# gatedriver_trafo_sma_compact_ACDC_ultra_.net
KiCad netlist of a schematic drawn in EAGLE
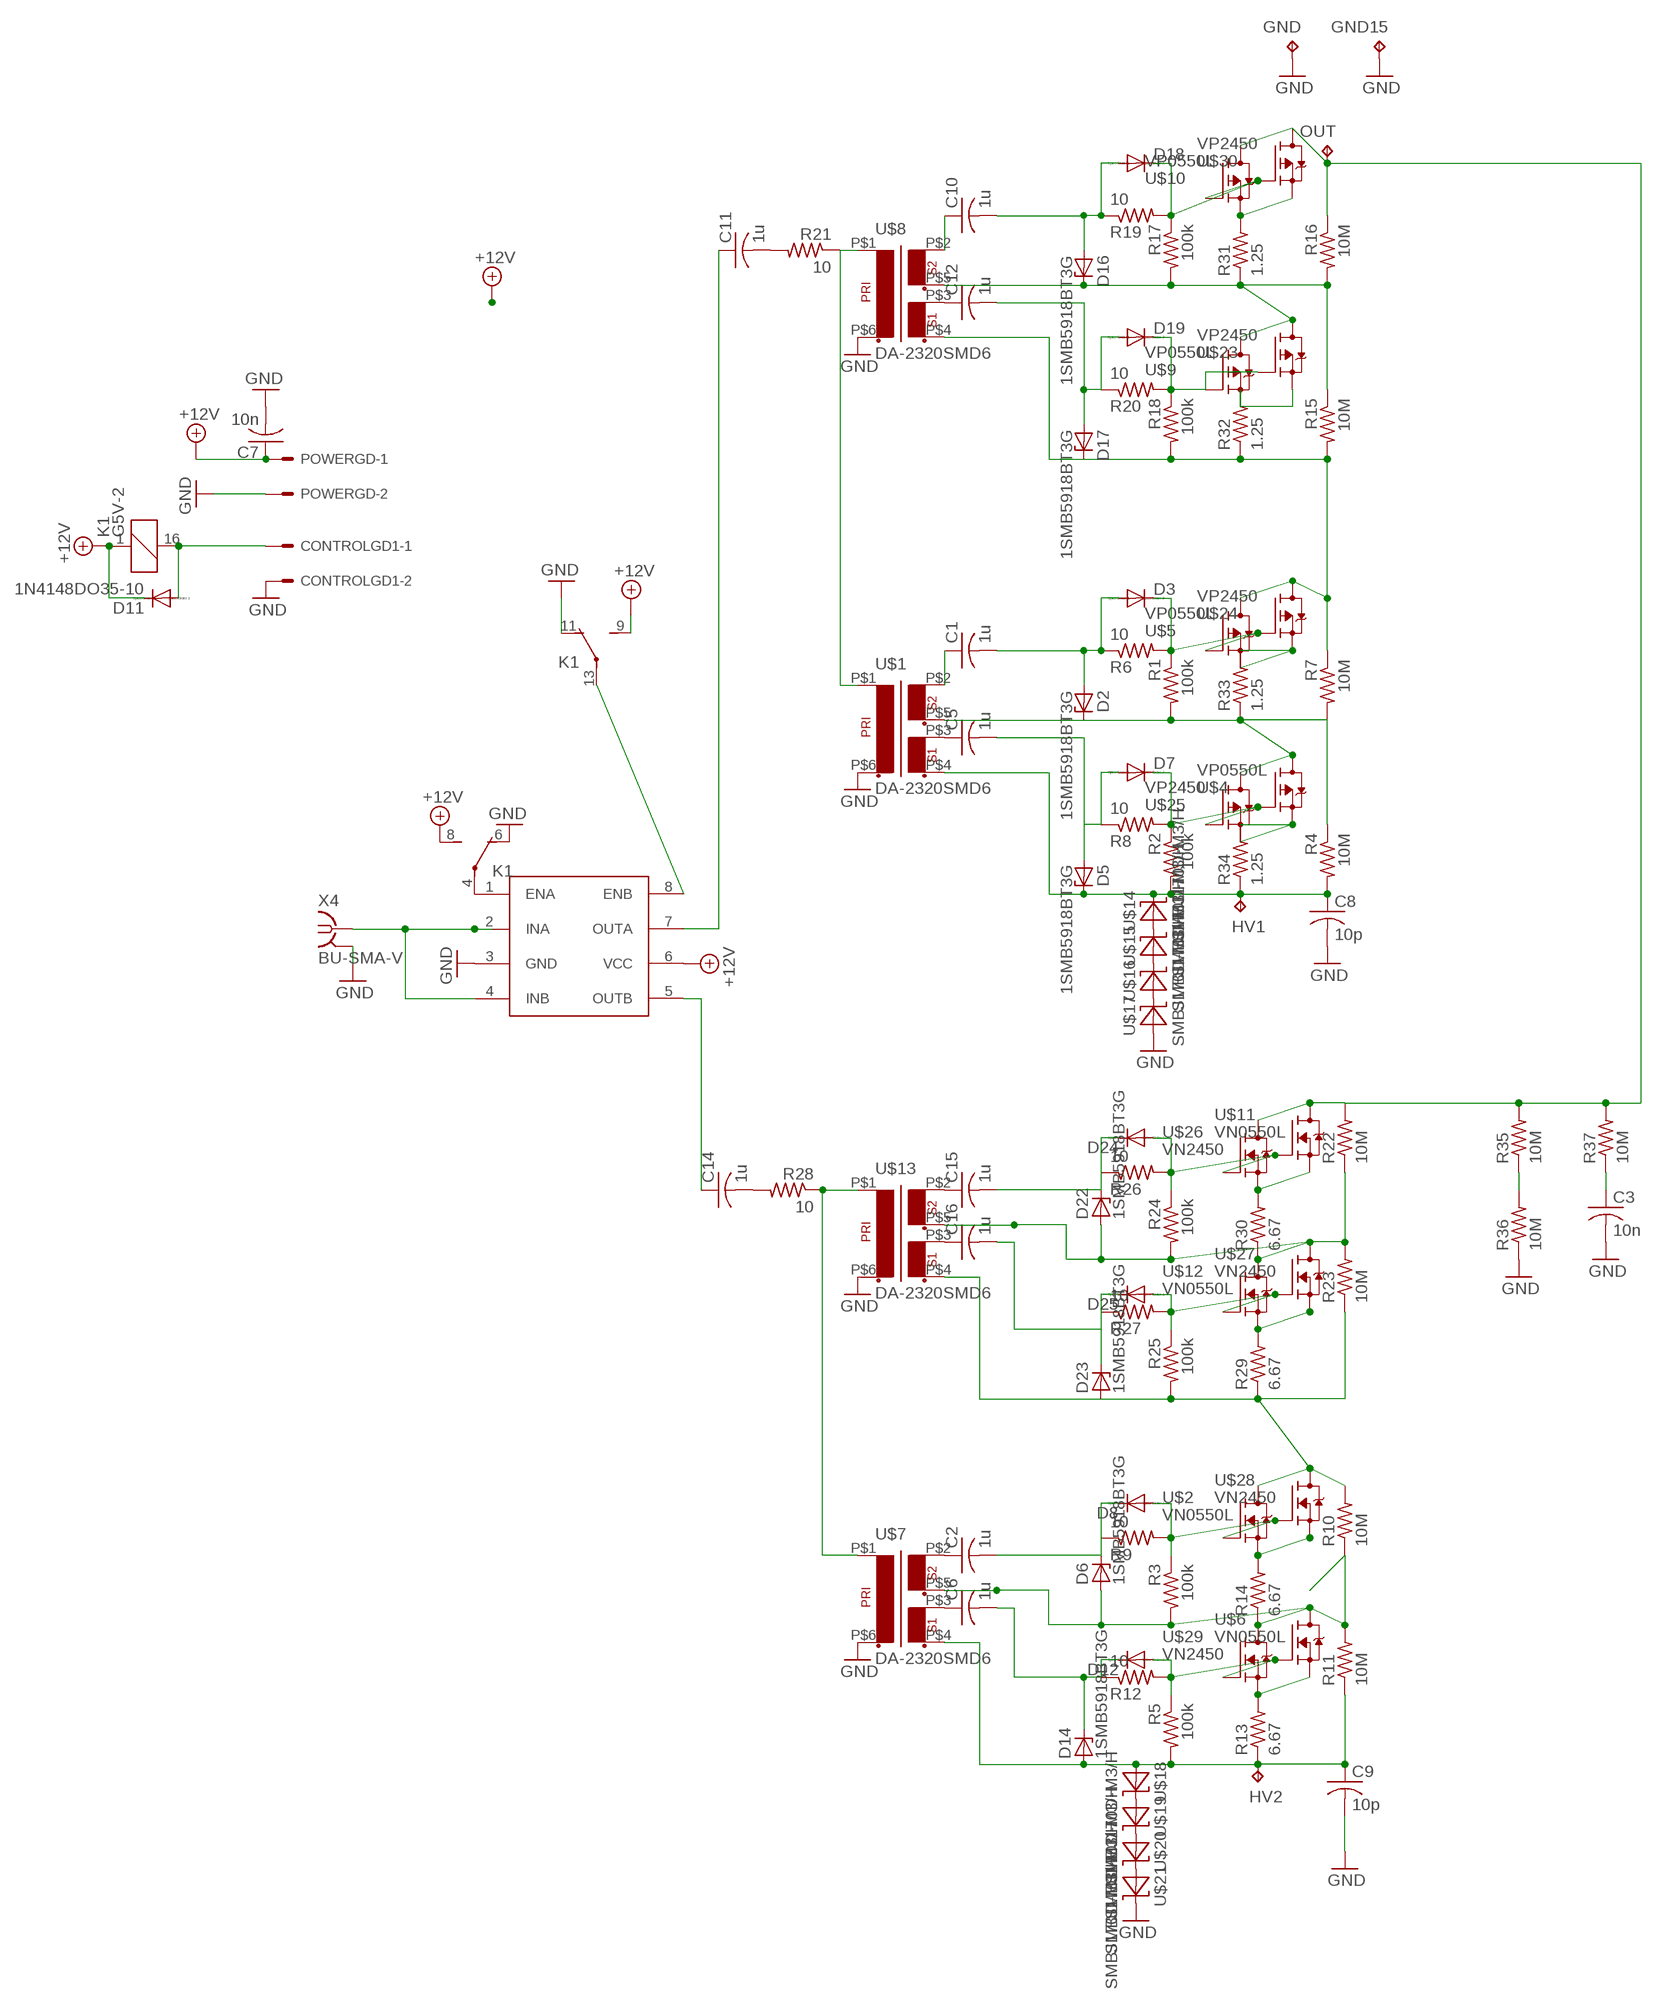
[diagram p0: schematic, sheet 1]

(export (version "E")
  (design (tool "Eeschema 10.0.6"))
  (components
    (comp (ref "C1")
      (value "1u")
      (footprint "eagle-import:C0805")
      (libsource (lib "eagle-import") (part "resistor_C-USC0805"))
    )
    (comp (ref "C2")
      (value "1u")
      (footprint "eagle-import:C0805")
      (libsource (lib "eagle-import") (part "resistor_C-USC0805"))
    )
    (comp (ref "C3")
      (value "10n")
      (footprint "eagle-import:C0805")
      (libsource (lib "eagle-import") (part "resistor_C-USC0805"))
    )
    (comp (ref "C5")
      (value "1u")
      (footprint "eagle-import:C0805")
      (libsource (lib "eagle-import") (part "resistor_C-USC0805"))
    )
    (comp (ref "C6")
      (value "1u")
      (footprint "eagle-import:C0805")
      (libsource (lib "eagle-import") (part "resistor_C-USC0805"))
    )
    (comp (ref "C7")
      (value "10n")
      (footprint "eagle-import:C050-030X075")
      (libsource (lib "eagle-import") (part "C-US050-030X075"))
    )
    (comp (ref "C8")
      (value "10p")
      (footprint "eagle-import:C102-064X133")
      (libsource (lib "eagle-import") (part "resistor_C-US102-064X133"))
    )
    (comp (ref "C9")
      (value "10p")
      (footprint "eagle-import:C102-064X133")
      (libsource (lib "eagle-import") (part "resistor_C-US102-064X133"))
    )
    (comp (ref "C10")
      (value "1u")
      (footprint "eagle-import:C0805")
      (libsource (lib "eagle-import") (part "resistor_C-USC0805"))
    )
    (comp (ref "C11")
      (value "1u")
      (footprint "eagle-import:C0805")
      (libsource (lib "eagle-import") (part "resistor_C-USC0805"))
    )
    (comp (ref "C12")
      (value "1u")
      (footprint "eagle-import:C0805")
      (libsource (lib "eagle-import") (part "resistor_C-USC0805"))
    )
    (comp (ref "C14")
      (value "1u")
      (footprint "eagle-import:C0805")
      (libsource (lib "eagle-import") (part "resistor_C-USC0805"))
    )
    (comp (ref "C15")
      (value "1u")
      (footprint "eagle-import:C0805")
      (libsource (lib "eagle-import") (part "resistor_C-USC0805"))
    )
    (comp (ref "C16")
      (value "1u")
      (footprint "eagle-import:C0805")
      (libsource (lib "eagle-import") (part "resistor_C-USC0805"))
    )
    (comp (ref "CONTROLGD1")
      (value "KK-156-2")
      (footprint "eagle-import:KK-156-2")
      (libsource (lib "eagle-import") (part "KK-156-2"))
    )
    (comp (ref "D2")
      (value "1SMB5918BT3G")
      (footprint "eagle-import:SMB")
      (libsource (lib "eagle-import") (part "ZENER-DIODESMB"))
    )
    (comp (ref "D3")
      (value "DIODE-SMB")
      (footprint "eagle-import:SMB")
      (libsource (lib "eagle-import") (part "DIODE-SMB"))
    )
    (comp (ref "D5")
      (value "1SMB5918BT3G")
      (footprint "eagle-import:SMB")
      (libsource (lib "eagle-import") (part "ZENER-DIODESMB"))
    )
    (comp (ref "D6")
      (value "1SMB5918BT3G")
      (footprint "eagle-import:SMB")
      (libsource (lib "eagle-import") (part "ZENER-DIODESMB"))
    )
    (comp (ref "D7")
      (value "DIODE-SMB")
      (footprint "eagle-import:SMB")
      (libsource (lib "eagle-import") (part "DIODE-SMB"))
    )
    (comp (ref "D8")
      (value "DIODE-SMB")
      (footprint "eagle-import:SMB")
      (libsource (lib "eagle-import") (part "DIODE-SMB"))
    )
    (comp (ref "D11")
      (value "1N4148DO35-10")
      (footprint "eagle-import:DO35-10")
      (libsource (lib "eagle-import") (part "1N4148DO35-10"))
    )
    (comp (ref "D12")
      (value "DIODE-SMB")
      (footprint "eagle-import:SMB")
      (libsource (lib "eagle-import") (part "DIODE-SMB"))
    )
    (comp (ref "D14")
      (value "1SMB5918BT3G")
      (footprint "eagle-import:SMB")
      (libsource (lib "eagle-import") (part "ZENER-DIODESMB"))
    )
    (comp (ref "D16")
      (value "1SMB5918BT3G")
      (footprint "eagle-import:SMB")
      (libsource (lib "eagle-import") (part "ZENER-DIODESMB"))
    )
    (comp (ref "D17")
      (value "1SMB5918BT3G")
      (footprint "eagle-import:SMB")
      (libsource (lib "eagle-import") (part "ZENER-DIODESMB"))
    )
    (comp (ref "D18")
      (value "DIODE-SMB")
      (footprint "eagle-import:SMB")
      (libsource (lib "eagle-import") (part "DIODE-SMB"))
    )
    (comp (ref "D19")
      (value "DIODE-SMB")
      (footprint "eagle-import:SMB")
      (libsource (lib "eagle-import") (part "DIODE-SMB"))
    )
    (comp (ref "D22")
      (value "1SMB5918BT3G")
      (footprint "eagle-import:SMB")
      (libsource (lib "eagle-import") (part "ZENER-DIODESMB"))
    )
    (comp (ref "D23")
      (value "1SMB5918BT3G")
      (footprint "eagle-import:SMB")
      (libsource (lib "eagle-import") (part "ZENER-DIODESMB"))
    )
    (comp (ref "D24")
      (value "DIODE-SMB")
      (footprint "eagle-import:SMB")
      (libsource (lib "eagle-import") (part "DIODE-SMB"))
    )
    (comp (ref "D25")
      (value "DIODE-SMB")
      (footprint "eagle-import:SMB")
      (libsource (lib "eagle-import") (part "DIODE-SMB"))
    )
    (comp (ref "GND")
      (value "TPPAD1-20Y")
      (footprint "eagle-import:P1-20Y")
      (libsource (lib "eagle-import") (part "TPPAD1-20Y"))
    )
    (comp (ref "GND15")
      (value "TPPAD1-20Y")
      (footprint "eagle-import:P1-20Y")
      (libsource (lib "eagle-import") (part "TPPAD1-20Y"))
    )
    (comp (ref "HV1")
      (value "TPPAD1-20Y")
      (footprint "eagle-import:P1-20Y")
      (libsource (lib "eagle-import") (part "TPPAD1-20Y"))
    )
    (comp (ref "HV2")
      (value "TPPAD1-20Y")
      (footprint "eagle-import:P1-20Y")
      (libsource (lib "eagle-import") (part "TPPAD1-20Y"))
    )
    (comp (ref "K1")
      (value "G5V-2")
      (footprint "eagle-import:G5V-2")
      (fields (field (name "MPN") "G5V-2 5DC"))
      (libsource (lib "eagle-import") (part "G5V-2"))
    )
    (comp (ref "OUT")
      (value "TPPAD1-20Y")
      (footprint "eagle-import:P1-20Y")
      (libsource (lib "eagle-import") (part "TPPAD1-20Y"))
    )
    (comp (ref "POWERGD")
      (value "KK-156-2")
      (footprint "eagle-import:KK-156-2")
      (libsource (lib "eagle-import") (part "KK-156-2"))
    )
    (comp (ref "R1")
      (value "100k")
      (footprint "eagle-import:R0805")
      (libsource (lib "eagle-import") (part "R-US_R0805"))
    )
    (comp (ref "R2")
      (value "100k")
      (footprint "eagle-import:R0805")
      (libsource (lib "eagle-import") (part "R-US_R0805"))
    )
    (comp (ref "R3")
      (value "100k")
      (footprint "eagle-import:R0805")
      (libsource (lib "eagle-import") (part "R-US_R0805"))
    )
    (comp (ref "R4")
      (value "10M")
      (footprint "eagle-import:R2512")
      (libsource (lib "eagle-import") (part "R-US_R2512"))
    )
    (comp (ref "R5")
      (value "100k")
      (footprint "eagle-import:R0805")
      (libsource (lib "eagle-import") (part "R-US_R0805"))
    )
    (comp (ref "R6")
      (value "10")
      (footprint "eagle-import:R0805")
      (libsource (lib "eagle-import") (part "R-US_R0805"))
    )
    (comp (ref "R7")
      (value "10M")
      (footprint "eagle-import:R2512")
      (libsource (lib "eagle-import") (part "R-US_R2512"))
    )
    (comp (ref "R8")
      (value "10")
      (footprint "eagle-import:R0805")
      (libsource (lib "eagle-import") (part "R-US_R0805"))
    )
    (comp (ref "R9")
      (value "10")
      (footprint "eagle-import:R0805")
      (libsource (lib "eagle-import") (part "R-US_R0805"))
    )
    (comp (ref "R10")
      (value "10M")
      (footprint "eagle-import:R2512")
      (libsource (lib "eagle-import") (part "R-US_R2512"))
    )
    (comp (ref "R11")
      (value "10M")
      (footprint "eagle-import:R2512")
      (libsource (lib "eagle-import") (part "R-US_R2512"))
    )
    (comp (ref "R12")
      (value "10")
      (footprint "eagle-import:R0805")
      (libsource (lib "eagle-import") (part "R-US_R0805"))
    )
    (comp (ref "R13")
      (value "6.67")
      (footprint "eagle-import:R0805")
      (libsource (lib "eagle-import") (part "R-US_R0805"))
    )
    (comp (ref "R14")
      (value "6.67")
      (footprint "eagle-import:R0805")
      (libsource (lib "eagle-import") (part "R-US_R0805"))
    )
    (comp (ref "R15")
      (value "10M")
      (footprint "eagle-import:R2512")
      (libsource (lib "eagle-import") (part "R-US_R2512"))
    )
    (comp (ref "R16")
      (value "10M")
      (footprint "eagle-import:R2512")
      (libsource (lib "eagle-import") (part "R-US_R2512"))
    )
    (comp (ref "R17")
      (value "100k")
      (footprint "eagle-import:R0805")
      (libsource (lib "eagle-import") (part "R-US_R0805"))
    )
    (comp (ref "R18")
      (value "100k")
      (footprint "eagle-import:R0805")
      (libsource (lib "eagle-import") (part "R-US_R0805"))
    )
    (comp (ref "R19")
      (value "10")
      (footprint "eagle-import:R0805")
      (libsource (lib "eagle-import") (part "R-US_R0805"))
    )
    (comp (ref "R20")
      (value "10")
      (footprint "eagle-import:R0805")
      (libsource (lib "eagle-import") (part "R-US_R0805"))
    )
    (comp (ref "R21")
      (value "10")
      (footprint "eagle-import:R0805")
      (libsource (lib "eagle-import") (part "R-US_R0805"))
    )
    (comp (ref "R22")
      (value "10M")
      (footprint "eagle-import:R2512")
      (libsource (lib "eagle-import") (part "R-US_R2512"))
    )
    (comp (ref "R23")
      (value "10M")
      (footprint "eagle-import:R2512")
      (libsource (lib "eagle-import") (part "R-US_R2512"))
    )
    (comp (ref "R24")
      (value "100k")
      (footprint "eagle-import:R0805")
      (libsource (lib "eagle-import") (part "R-US_R0805"))
    )
    (comp (ref "R25")
      (value "100k")
      (footprint "eagle-import:R0805")
      (libsource (lib "eagle-import") (part "R-US_R0805"))
    )
    (comp (ref "R26")
      (value "10")
      (footprint "eagle-import:R0805")
      (libsource (lib "eagle-import") (part "R-US_R0805"))
    )
    (comp (ref "R27")
      (value "10")
      (footprint "eagle-import:R0805")
      (libsource (lib "eagle-import") (part "R-US_R0805"))
    )
    (comp (ref "R28")
      (value "10")
      (footprint "eagle-import:R0805")
      (libsource (lib "eagle-import") (part "R-US_R0805"))
    )
    (comp (ref "R29")
      (value "6.67")
      (footprint "eagle-import:R0805")
      (libsource (lib "eagle-import") (part "R-US_R0805"))
    )
    (comp (ref "R30")
      (value "6.67")
      (footprint "eagle-import:R0805")
      (libsource (lib "eagle-import") (part "R-US_R0805"))
    )
    (comp (ref "R31")
      (value "1.25")
      (footprint "eagle-import:R0805")
      (libsource (lib "eagle-import") (part "R-US_R0805"))
    )
    (comp (ref "R32")
      (value "1.25")
      (footprint "eagle-import:R0805")
      (libsource (lib "eagle-import") (part "R-US_R0805"))
    )
    (comp (ref "R33")
      (value "1.25")
      (footprint "eagle-import:R0805")
      (libsource (lib "eagle-import") (part "R-US_R0805"))
    )
    (comp (ref "R34")
      (value "1.25")
      (footprint "eagle-import:R0805")
      (libsource (lib "eagle-import") (part "R-US_R0805"))
    )
    (comp (ref "R35")
      (value "10M")
      (footprint "eagle-import:R2512")
      (libsource (lib "eagle-import") (part "R-US_R2512"))
    )
    (comp (ref "R36")
      (value "10M")
      (footprint "eagle-import:R2512")
      (libsource (lib "eagle-import") (part "R-US_R2512"))
    )
    (comp (ref "R37")
      (value "10M")
      (footprint "eagle-import:R2512")
      (libsource (lib "eagle-import") (part "R-US_R2512"))
    )
    (comp (ref "U$1")
      (value "DA-2320SMD6")
      (footprint "eagle-import:SMD6")
      (libsource (lib "eagle-import") (part "DA-2320SMD6"))
    )
    (comp (ref "U$2")
      (value "VN0550L")
      (footprint "eagle-import:TO92L")
      (libsource (lib "eagle-import") (part "VN0550L"))
    )
    (comp (ref "U$3")
      (value "UCC27425")
      (footprint "eagle-import:DIL08")
      (libsource (lib "eagle-import") (part "UCC27425"))
    )
    (comp (ref "U$4")
      (value "VP0550L")
      (footprint "eagle-import:TO92L")
      (libsource (lib "eagle-import") (part "VP0550L"))
    )
    (comp (ref "U$5")
      (value "VP0550L")
      (footprint "eagle-import:TO92L")
      (libsource (lib "eagle-import") (part "VP0550L"))
    )
    (comp (ref "U$6")
      (value "VN0550L")
      (footprint "eagle-import:TO92L")
      (libsource (lib "eagle-import") (part "VN0550L"))
    )
    (comp (ref "U$7")
      (value "DA-2320SMD6")
      (footprint "eagle-import:SMD6")
      (libsource (lib "eagle-import") (part "DA-2320SMD6"))
    )
    (comp (ref "U$8")
      (value "DA-2320SMD6")
      (footprint "eagle-import:SMD6")
      (libsource (lib "eagle-import") (part "DA-2320SMD6"))
    )
    (comp (ref "U$9")
      (value "VP0550L")
      (footprint "eagle-import:TO92L")
      (libsource (lib "eagle-import") (part "VP0550L"))
    )
    (comp (ref "U$10")
      (value "VP0550L")
      (footprint "eagle-import:TO92L")
      (libsource (lib "eagle-import") (part "VP0550L"))
    )
    (comp (ref "U$11")
      (value "VN0550L")
      (footprint "eagle-import:TO92L")
      (libsource (lib "eagle-import") (part "VN0550L"))
    )
    (comp (ref "U$12")
      (value "VN0550L")
      (footprint "eagle-import:TO92L")
      (libsource (lib "eagle-import") (part "VN0550L"))
    )
    (comp (ref "U$13")
      (value "DA-2320SMD6")
      (footprint "eagle-import:SMD6")
      (libsource (lib "eagle-import") (part "DA-2320SMD6"))
    )
    (comp (ref "U$14")
      (value "SMBJ170D-M3/H")
      (footprint "eagle-import:DO214AA")
      (libsource (lib "eagle-import") (part "SMBJ170D-M3/H"))
    )
    (comp (ref "U$15")
      (value "SMBJ170D-M3/H")
      (footprint "eagle-import:DO214AA")
      (libsource (lib "eagle-import") (part "SMBJ170D-M3/H"))
    )
    (comp (ref "U$16")
      (value "SMBJ170D-M3/H")
      (footprint "eagle-import:DO214AA")
      (libsource (lib "eagle-import") (part "SMBJ170D-M3/H"))
    )
    (comp (ref "U$17")
      (value "SMBJ170D-M3/H")
      (footprint "eagle-import:DO214AA")
      (libsource (lib "eagle-import") (part "SMBJ170D-M3/H"))
    )
    (comp (ref "U$18")
      (value "SMBJ170D-M3/H")
      (footprint "eagle-import:DO214AA")
      (libsource (lib "eagle-import") (part "SMBJ170D-M3/H"))
    )
    (comp (ref "U$19")
      (value "SMBJ170D-M3/H")
      (footprint "eagle-import:DO214AA")
      (libsource (lib "eagle-import") (part "SMBJ170D-M3/H"))
    )
    (comp (ref "U$20")
      (value "SMBJ170D-M3/H")
      (footprint "eagle-import:DO214AA")
      (libsource (lib "eagle-import") (part "SMBJ170D-M3/H"))
    )
    (comp (ref "U$21")
      (value "SMBJ170D-M3/H")
      (footprint "eagle-import:DO214AA")
      (libsource (lib "eagle-import") (part "SMBJ170D-M3/H"))
    )
    (comp (ref "U$23")
      (value "VP2450")
      (footprint "eagle-import:SOT89-BCE")
      (libsource (lib "eagle-import") (part "VP2450"))
    )
    (comp (ref "U$24")
      (value "VP2450")
      (footprint "eagle-import:SOT89-BCE")
      (libsource (lib "eagle-import") (part "VP2450"))
    )
    (comp (ref "U$25")
      (value "VP2450")
      (footprint "eagle-import:SOT89-BCE")
      (libsource (lib "eagle-import") (part "VP2450"))
    )
    (comp (ref "U$26")
      (value "VN2450")
      (footprint "eagle-import:SOT89-BCE")
      (libsource (lib "eagle-import") (part "VN2450"))
    )
    (comp (ref "U$27")
      (value "VN2450")
      (footprint "eagle-import:SOT89-BCE")
      (libsource (lib "eagle-import") (part "VN2450"))
    )
    (comp (ref "U$28")
      (value "VN2450")
      (footprint "eagle-import:SOT89-BCE")
      (libsource (lib "eagle-import") (part "VN2450"))
    )
    (comp (ref "U$29")
      (value "VN2450")
      (footprint "eagle-import:SOT89-BCE")
      (libsource (lib "eagle-import") (part "VN2450"))
    )
    (comp (ref "U$30")
      (value "VP2450")
      (footprint "eagle-import:SOT89-BCE")
      (libsource (lib "eagle-import") (part "VP2450"))
    )
    (comp (ref "X4")
      (value "BU-SMA-V")
      (footprint "eagle-import:BU-SMA-V")
      (libsource (lib "eagle-import") (part "BU-SMA-V"))
    )
  )
  (nets
    (net (code "1") (name "+12V") (class "Default")
      (node (ref "C7") (pin "1") (pinfunction "1_1") (pintype "passive"))
      (node (ref "D11") (pin "C") (pinfunction "C_C") (pintype "passive"))
      (node (ref "K1") (pin "1") (pinfunction "1_1") (pintype "passive"))
      (node (ref "K1") (pin "8") (pinfunction "S_8") (pintype "passive"))
      (node (ref "K1") (pin "9") (pinfunction "S_9") (pintype "passive"))
      (node (ref "POWERGD") (pin "1") (pinfunction "S_1") (pintype "passive"))
      (node (ref "U$3") (pin "6") (pinfunction "VCC_6") (pintype "bidirectional"))
    )
    (net (code "2") (name "GND") (class "Default")
      (node (ref "C3") (pin "2") (pinfunction "2_2") (pintype "passive"))
      (node (ref "C7") (pin "2") (pinfunction "2_2") (pintype "passive"))
      (node (ref "C8") (pin "2") (pinfunction "2_2") (pintype "passive"))
      (node (ref "C9") (pin "2") (pinfunction "2_2") (pintype "passive"))
      (node (ref "CONTROLGD1") (pin "2") (pinfunction "S_2") (pintype "passive"))
      (node (ref "GND") (pin "TP") (pinfunction "TP_TP") (pintype "input"))
      (node (ref "GND15") (pin "TP") (pinfunction "TP_TP") (pintype "input"))
      (node (ref "K1") (pin "11") (pinfunction "O_11") (pintype "passive"))
      (node (ref "K1") (pin "6") (pinfunction "O_6") (pintype "passive"))
      (node (ref "POWERGD") (pin "2") (pinfunction "S_2") (pintype "passive"))
      (node (ref "R36") (pin "1") (pinfunction "1_1") (pintype "passive"))
      (node (ref "U$1") (pin "P$6") (pinfunction "2_P$6") (pintype "passive"))
      (node (ref "U$13") (pin "P$6") (pinfunction "2_P$6") (pintype "passive"))
      (node (ref "U$17") (pin "A") (pinfunction "A_A") (pintype "passive"))
      (node (ref "U$21") (pin "C") (pinfunction "C_C") (pintype "passive"))
      (node (ref "U$3") (pin "3") (pinfunction "GND_3") (pintype "bidirectional"))
      (node (ref "U$7") (pin "P$6") (pinfunction "2_P$6") (pintype "passive"))
      (node (ref "U$8") (pin "P$6") (pinfunction "2_P$6") (pintype "passive"))
      (node (ref "X4") (pin "2") (pinfunction "2_2") (pintype "passive"))
      (node (ref "X4") (pin "3") (pinfunction "2_3") (pintype "passive"))
      (node (ref "X4") (pin "4") (pinfunction "2_4") (pintype "passive"))
      (node (ref "X4") (pin "5") (pinfunction "2_5") (pintype "passive"))
    )
    (net (code "3") (name "Net-(C1-Pad2)") (class "Default")
      (node (ref "C1") (pin "2") (pinfunction "2_2") (pintype "passive"))
      (node (ref "D2") (pin "A") (pinfunction "A_A") (pintype "passive"))
      (node (ref "D3") (pin "A") (pinfunction "A_A") (pintype "passive"))
      (node (ref "R6") (pin "1") (pinfunction "1_1") (pintype "passive"))
    )
    (net (code "4") (name "Net-(C2-Pad2)") (class "Default")
      (node (ref "C2") (pin "2") (pinfunction "2_2") (pintype "passive"))
      (node (ref "D6") (pin "C") (pinfunction "C_C") (pintype "passive"))
      (node (ref "D8") (pin "C") (pinfunction "C_C") (pintype "passive"))
      (node (ref "R9") (pin "1") (pinfunction "1_1") (pintype "passive"))
    )
    (net (code "5") (name "Net-(C3-Pad1)") (class "Default")
      (node (ref "C3") (pin "1") (pinfunction "1_1") (pintype "passive"))
      (node (ref "R37") (pin "1") (pinfunction "1_1") (pintype "passive"))
    )
    (net (code "6") (name "Net-(C5-Pad2)") (class "Default")
      (node (ref "C5") (pin "2") (pinfunction "2_2") (pintype "passive"))
      (node (ref "D5") (pin "A") (pinfunction "A_A") (pintype "passive"))
      (node (ref "D7") (pin "A") (pinfunction "A_A") (pintype "passive"))
      (node (ref "R8") (pin "1") (pinfunction "1_1") (pintype "passive"))
    )
    (net (code "7") (name "Net-(C6-Pad2)") (class "Default")
      (node (ref "C6") (pin "2") (pinfunction "2_2") (pintype "passive"))
      (node (ref "D12") (pin "C") (pinfunction "C_C") (pintype "passive"))
      (node (ref "D14") (pin "C") (pinfunction "C_C") (pintype "passive"))
      (node (ref "R12") (pin "1") (pinfunction "1_1") (pintype "passive"))
    )
    (net (code "8") (name "Net-(C10-Pad2)") (class "Default")
      (node (ref "C10") (pin "2") (pinfunction "2_2") (pintype "passive"))
      (node (ref "D16") (pin "A") (pinfunction "A_A") (pintype "passive"))
      (node (ref "D18") (pin "A") (pinfunction "A_A") (pintype "passive"))
      (node (ref "R19") (pin "1") (pinfunction "1_1") (pintype "passive"))
    )
    (net (code "9") (name "Net-(C11-Pad2)") (class "Default")
      (node (ref "C11") (pin "2") (pinfunction "2_2") (pintype "passive"))
      (node (ref "R21") (pin "2") (pinfunction "2_2") (pintype "passive"))
    )
    (net (code "10") (name "Net-(C12-Pad2)") (class "Default")
      (node (ref "C12") (pin "2") (pinfunction "2_2") (pintype "passive"))
      (node (ref "D17") (pin "A") (pinfunction "A_A") (pintype "passive"))
      (node (ref "D19") (pin "A") (pinfunction "A_A") (pintype "passive"))
      (node (ref "R20") (pin "1") (pinfunction "1_1") (pintype "passive"))
    )
    (net (code "11") (name "Net-(C14-Pad2)") (class "Default")
      (node (ref "C14") (pin "2") (pinfunction "2_2") (pintype "passive"))
      (node (ref "R28") (pin "2") (pinfunction "2_2") (pintype "passive"))
    )
    (net (code "12") (name "Net-(C15-Pad2)") (class "Default")
      (node (ref "C15") (pin "2") (pinfunction "2_2") (pintype "passive"))
      (node (ref "D22") (pin "C") (pinfunction "C_C") (pintype "passive"))
      (node (ref "D24") (pin "C") (pinfunction "C_C") (pintype "passive"))
      (node (ref "R26") (pin "1") (pinfunction "1_1") (pintype "passive"))
    )
    (net (code "13") (name "Net-(C16-Pad2)") (class "Default")
      (node (ref "C16") (pin "2") (pinfunction "2_2") (pintype "passive"))
      (node (ref "D23") (pin "C") (pinfunction "C_C") (pintype "passive"))
      (node (ref "D25") (pin "C") (pinfunction "C_C") (pintype "passive"))
      (node (ref "R27") (pin "1") (pinfunction "1_1") (pintype "passive"))
    )
    (net (code "14") (name "Net-(CONTROLGD1A-S)") (class "Default")
      (node (ref "CONTROLGD1") (pin "1") (pinfunction "S_1") (pintype "passive"))
      (node (ref "D11") (pin "A") (pinfunction "A_A") (pintype "passive"))
      (node (ref "K1") (pin "16") (pinfunction "2_16") (pintype "passive"))
    )
    (net (code "15") (name "Net-(K1A-P)") (class "Default")
      (node (ref "K1") (pin "4") (pinfunction "P_4") (pintype "passive"))
      (node (ref "U$3") (pin "1") (pinfunction "ENA_1") (pintype "bidirectional"))
    )
    (net (code "16") (name "Net-(K1B-P)") (class "Default")
      (node (ref "K1") (pin "13") (pinfunction "P_13") (pintype "passive"))
      (node (ref "U$3") (pin "8") (pinfunction "ENB_8") (pintype "bidirectional"))
    )
    (net (code "17") (name "Net-(R35-Pad1)") (class "Default")
      (node (ref "R35") (pin "1") (pinfunction "1_1") (pintype "passive"))
      (node (ref "R36") (pin "2") (pinfunction "2_2") (pintype "passive"))
    )
    (net (code "18") (name "Net-(U$1-1)") (class "Default")
      (node (ref "R21") (pin "1") (pinfunction "1_1") (pintype "passive"))
      (node (ref "U$1") (pin "P$1") (pinfunction "1_P$1") (pintype "passive"))
      (node (ref "U$8") (pin "P$1") (pinfunction "1_P$1") (pintype "passive"))
    )
    (net (code "19") (name "Net-(U$1-3)") (class "Default")
      (node (ref "C8") (pin "1") (pinfunction "1_1") (pintype "passive"))
      (node (ref "D5") (pin "C") (pinfunction "C_C") (pintype "passive"))
      (node (ref "HV1") (pin "TP") (pinfunction "TP_TP") (pintype "input"))
      (node (ref "R2") (pin "2") (pinfunction "2_2") (pintype "passive"))
      (node (ref "R34") (pin "1") (pinfunction "1_1") (pintype "passive"))
      (node (ref "R4") (pin "2") (pinfunction "2_2") (pintype "passive"))
      (node (ref "U$1") (pin "P$4") (pinfunction "3_P$4") (pintype "passive"))
      (node (ref "U$14") (pin "C") (pinfunction "C_C") (pintype "passive"))
    )
    (net (code "20") (name "Net-(U$1-4)") (class "Default")
      (node (ref "C5") (pin "1") (pinfunction "1_1") (pintype "passive"))
      (node (ref "U$1") (pin "P$3") (pinfunction "4_P$3") (pintype "passive"))
    )
    (net (code "21") (name "Net-(U$1-5)") (class "Default")
      (node (ref "D2") (pin "C") (pinfunction "C_C") (pintype "passive"))
      (node (ref "R1") (pin "2") (pinfunction "2_2") (pintype "passive"))
      (node (ref "R33") (pin "1") (pinfunction "1_1") (pintype "passive"))
      (node (ref "R4") (pin "1") (pinfunction "1_1") (pintype "passive"))
      (node (ref "R7") (pin "2") (pinfunction "2_2") (pintype "passive"))
      (node (ref "U$1") (pin "P$5") (pinfunction "5_P$5") (pintype "passive"))
      (node (ref "U$25") (pin "C") (pinfunction "D_C") (pintype "passive"))
      (node (ref "U$25") (pin "C@1") (pinfunction "D_C@1") (pintype "passive"))
      (node (ref "U$4") (pin "1") (pinfunction "D_1") (pintype "passive"))
    )
    (net (code "22") (name "Net-(U$1-6)") (class "Default")
      (node (ref "C1") (pin "1") (pinfunction "1_1") (pintype "passive"))
      (node (ref "U$1") (pin "P$2") (pinfunction "6_P$2") (pintype "passive"))
    )
    (net (code "23") (name "Net-(U$2-G)") (class "Default")
      (node (ref "D8") (pin "A") (pinfunction "A_A") (pintype "passive"))
      (node (ref "R3") (pin "1") (pinfunction "1_1") (pintype "passive"))
      (node (ref "R9") (pin "2") (pinfunction "2_2") (pintype "passive"))
      (node (ref "U$2") (pin "2") (pinfunction "G_2") (pintype "passive"))
      (node (ref "U$28") (pin "B") (pinfunction "G_B") (pintype "passive"))
    )
    (net (code "24") (name "Net-(U$2-S)") (class "Default")
      (node (ref "R14") (pin "2") (pinfunction "2_2") (pintype "passive"))
      (node (ref "U$2") (pin "3") (pinfunction "S_3") (pintype "passive"))
      (node (ref "U$28") (pin "E") (pinfunction "S_E") (pintype "passive"))
    )
    (net (code "25") (name "Net-(U$3-INA)") (class "Default")
      (node (ref "U$3") (pin "2") (pinfunction "INA_2") (pintype "bidirectional"))
      (node (ref "U$3") (pin "4") (pinfunction "INB_4") (pintype "bidirectional"))
      (node (ref "X4") (pin "1") (pinfunction "1_1") (pintype "passive"))
    )
    (net (code "26") (name "Net-(U$3-OUTA)") (class "Default")
      (node (ref "C11") (pin "1") (pinfunction "1_1") (pintype "passive"))
      (node (ref "U$3") (pin "7") (pinfunction "OUTA_7") (pintype "bidirectional"))
    )
    (net (code "27") (name "Net-(U$3-OUTB)") (class "Default")
      (node (ref "C14") (pin "1") (pinfunction "1_1") (pintype "passive"))
      (node (ref "U$3") (pin "5") (pinfunction "OUTB_5") (pintype "bidirectional"))
    )
    (net (code "28") (name "Net-(U$5-D)") (class "Default")
      (node (ref "D17") (pin "C") (pinfunction "C_C") (pintype "passive"))
      (node (ref "R15") (pin "2") (pinfunction "2_2") (pintype "passive"))
      (node (ref "R18") (pin "2") (pinfunction "2_2") (pintype "passive"))
      (node (ref "R32") (pin "1") (pinfunction "1_1") (pintype "passive"))
      (node (ref "R7") (pin "1") (pinfunction "1_1") (pintype "passive"))
      (node (ref "U$24") (pin "C") (pinfunction "D_C") (pintype "passive"))
      (node (ref "U$24") (pin "C@1") (pinfunction "D_C@1") (pintype "passive"))
      (node (ref "U$5") (pin "1") (pinfunction "D_1") (pintype "passive"))
      (node (ref "U$8") (pin "P$4") (pinfunction "3_P$4") (pintype "passive"))
    )
    (net (code "29") (name "Net-(U$6-D)") (class "Default")
      (node (ref "D6") (pin "A") (pinfunction "A_A") (pintype "passive"))
      (node (ref "R10") (pin "1") (pinfunction "1_1") (pintype "passive"))
      (node (ref "R11") (pin "2") (pinfunction "2_2") (pintype "passive"))
      (node (ref "R14") (pin "1") (pinfunction "1_1") (pintype "passive"))
      (node (ref "R3") (pin "2") (pinfunction "2_2") (pintype "passive"))
      (node (ref "U$29") (pin "C") (pinfunction "D_C") (pintype "passive"))
      (node (ref "U$29") (pin "C@1") (pinfunction "D_C@1") (pintype "passive"))
      (node (ref "U$6") (pin "1") (pinfunction "D_1") (pintype "passive"))
      (node (ref "U$7") (pin "P$5") (pinfunction "5_P$5") (pintype "passive"))
    )
    (net (code "30") (name "Net-(U$7-3)") (class "Default")
      (node (ref "C9") (pin "1") (pinfunction "1_1") (pintype "passive"))
      (node (ref "D14") (pin "A") (pinfunction "A_A") (pintype "passive"))
      (node (ref "HV2") (pin "TP") (pinfunction "TP_TP") (pintype "input"))
      (node (ref "R11") (pin "1") (pinfunction "1_1") (pintype "passive"))
      (node (ref "R13") (pin "1") (pinfunction "1_1") (pintype "passive"))
      (node (ref "R5") (pin "2") (pinfunction "2_2") (pintype "passive"))
      (node (ref "U$18") (pin "A") (pinfunction "A_A") (pintype "passive"))
      (node (ref "U$7") (pin "P$4") (pinfunction "3_P$4") (pintype "passive"))
    )
    (net (code "31") (name "Net-(U$7-4)") (class "Default")
      (node (ref "C6") (pin "1") (pinfunction "1_1") (pintype "passive"))
      (node (ref "U$7") (pin "P$3") (pinfunction "4_P$3") (pintype "passive"))
    )
    (net (code "32") (name "Net-(U$7-6)") (class "Default")
      (node (ref "C2") (pin "1") (pinfunction "1_1") (pintype "passive"))
      (node (ref "U$7") (pin "P$2") (pinfunction "6_P$2") (pintype "passive"))
    )
    (net (code "33") (name "Net-(U$8-4)") (class "Default")
      (node (ref "C12") (pin "1") (pinfunction "1_1") (pintype "passive"))
      (node (ref "U$8") (pin "P$3") (pinfunction "4_P$3") (pintype "passive"))
    )
    (net (code "34") (name "Net-(U$8-5)") (class "Default")
      (node (ref "D16") (pin "C") (pinfunction "C_C") (pintype "passive"))
      (node (ref "R15") (pin "1") (pinfunction "1_1") (pintype "passive"))
      (node (ref "R16") (pin "2") (pinfunction "2_2") (pintype "passive"))
      (node (ref "R17") (pin "2") (pinfunction "2_2") (pintype "passive"))
      (node (ref "R31") (pin "1") (pinfunction "1_1") (pintype "passive"))
      (node (ref "U$23") (pin "C") (pinfunction "D_C") (pintype "passive"))
      (node (ref "U$23") (pin "C@1") (pinfunction "D_C@1") (pintype "passive"))
      (node (ref "U$8") (pin "P$5") (pinfunction "5_P$5") (pintype "passive"))
      (node (ref "U$9") (pin "1") (pinfunction "D_1") (pintype "passive"))
    )
    (net (code "35") (name "Net-(U$8-6)") (class "Default")
      (node (ref "C10") (pin "1") (pinfunction "1_1") (pintype "passive"))
      (node (ref "U$8") (pin "P$2") (pinfunction "6_P$2") (pintype "passive"))
    )
    (net (code "36") (name "Net-(U$10-D)") (class "Default")
      (node (ref "OUT") (pin "TP") (pinfunction "TP_TP") (pintype "input"))
      (node (ref "R16") (pin "1") (pinfunction "1_1") (pintype "passive"))
      (node (ref "R22") (pin "2") (pinfunction "2_2") (pintype "passive"))
      (node (ref "R35") (pin "2") (pinfunction "2_2") (pintype "passive"))
      (node (ref "R37") (pin "2") (pinfunction "2_2") (pintype "passive"))
      (node (ref "U$10") (pin "1") (pinfunction "D_1") (pintype "passive"))
      (node (ref "U$11") (pin "1") (pinfunction "D_1") (pintype "passive"))
      (node (ref "U$26") (pin "C") (pinfunction "D_C") (pintype "passive"))
      (node (ref "U$26") (pin "C@1") (pinfunction "D_C@1") (pintype "passive"))
      (node (ref "U$30") (pin "C") (pinfunction "D_C") (pintype "passive"))
      (node (ref "U$30") (pin "C@1") (pinfunction "D_C@1") (pintype "passive"))
    )
    (net (code "37") (name "Net-(U$10-G)") (class "Default")
      (node (ref "D18") (pin "C") (pinfunction "C_C") (pintype "passive"))
      (node (ref "R17") (pin "1") (pinfunction "1_1") (pintype "passive"))
      (node (ref "R19") (pin "2") (pinfunction "2_2") (pintype "passive"))
      (node (ref "U$10") (pin "2") (pinfunction "G_2") (pintype "passive"))
      (node (ref "U$30") (pin "B") (pinfunction "G_B") (pintype "passive"))
    )
    (net (code "38") (name "Net-(U$10-S)") (class "Default")
      (node (ref "R31") (pin "2") (pinfunction "2_2") (pintype "passive"))
      (node (ref "U$10") (pin "3") (pinfunction "S_3") (pintype "passive"))
      (node (ref "U$30") (pin "E") (pinfunction "S_E") (pintype "passive"))
    )
    (net (code "39") (name "Net-(U$11-G)") (class "Default")
      (node (ref "D24") (pin "A") (pinfunction "A_A") (pintype "passive"))
      (node (ref "R24") (pin "1") (pinfunction "1_1") (pintype "passive"))
      (node (ref "R26") (pin "2") (pinfunction "2_2") (pintype "passive"))
      (node (ref "U$11") (pin "2") (pinfunction "G_2") (pintype "passive"))
      (node (ref "U$26") (pin "B") (pinfunction "G_B") (pintype "passive"))
    )
    (net (code "40") (name "Net-(U$11-S)") (class "Default")
      (node (ref "R30") (pin "2") (pinfunction "2_2") (pintype "passive"))
      (node (ref "U$11") (pin "3") (pinfunction "S_3") (pintype "passive"))
      (node (ref "U$26") (pin "E") (pinfunction "S_E") (pintype "passive"))
    )
    (net (code "41") (name "Net-(U$12-D)") (class "Default")
      (node (ref "D22") (pin "A") (pinfunction "A_A") (pintype "passive"))
      (node (ref "R22") (pin "1") (pinfunction "1_1") (pintype "passive"))
      (node (ref "R23") (pin "2") (pinfunction "2_2") (pintype "passive"))
      (node (ref "R24") (pin "2") (pinfunction "2_2") (pintype "passive"))
      (node (ref "R30") (pin "1") (pinfunction "1_1") (pintype "passive"))
      (node (ref "U$12") (pin "1") (pinfunction "D_1") (pintype "passive"))
      (node (ref "U$13") (pin "P$5") (pinfunction "5_P$5") (pintype "passive"))
      (node (ref "U$27") (pin "C") (pinfunction "D_C") (pintype "passive"))
      (node (ref "U$27") (pin "C@1") (pinfunction "D_C@1") (pintype "passive"))
    )
    (net (code "42") (name "Net-(U$12-G)") (class "Default")
      (node (ref "D25") (pin "A") (pinfunction "A_A") (pintype "passive"))
      (node (ref "R25") (pin "1") (pinfunction "1_1") (pintype "passive"))
      (node (ref "R27") (pin "2") (pinfunction "2_2") (pintype "passive"))
      (node (ref "U$12") (pin "2") (pinfunction "G_2") (pintype "passive"))
      (node (ref "U$27") (pin "B") (pinfunction "G_B") (pintype "passive"))
    )
    (net (code "43") (name "Net-(U$12-S)") (class "Default")
      (node (ref "R29") (pin "2") (pinfunction "2_2") (pintype "passive"))
      (node (ref "U$12") (pin "3") (pinfunction "S_3") (pintype "passive"))
      (node (ref "U$27") (pin "E") (pinfunction "S_E") (pintype "passive"))
    )
    (net (code "44") (name "Net-(U$13-1)") (class "Default")
      (node (ref "R28") (pin "1") (pinfunction "1_1") (pintype "passive"))
      (node (ref "U$13") (pin "P$1") (pinfunction "1_P$1") (pintype "passive"))
      (node (ref "U$7") (pin "P$1") (pinfunction "1_P$1") (pintype "passive"))
    )
    (net (code "45") (name "Net-(U$13-3)") (class "Default")
      (node (ref "D23") (pin "A") (pinfunction "A_A") (pintype "passive"))
      (node (ref "R10") (pin "2") (pinfunction "2_2") (pintype "passive"))
      (node (ref "R23") (pin "1") (pinfunction "1_1") (pintype "passive"))
      (node (ref "R25") (pin "2") (pinfunction "2_2") (pintype "passive"))
      (node (ref "R29") (pin "1") (pinfunction "1_1") (pintype "passive"))
      (node (ref "U$13") (pin "P$4") (pinfunction "3_P$4") (pintype "passive"))
      (node (ref "U$2") (pin "1") (pinfunction "D_1") (pintype "passive"))
      (node (ref "U$28") (pin "C") (pinfunction "D_C") (pintype "passive"))
      (node (ref "U$28") (pin "C@1") (pinfunction "D_C@1") (pintype "passive"))
    )
    (net (code "46") (name "Net-(U$13-4)") (class "Default")
      (node (ref "C16") (pin "1") (pinfunction "1_1") (pintype "passive"))
      (node (ref "U$13") (pin "P$3") (pinfunction "4_P$3") (pintype "passive"))
    )
    (net (code "47") (name "Net-(U$13-6)") (class "Default")
      (node (ref "C15") (pin "1") (pinfunction "1_1") (pintype "passive"))
      (node (ref "U$13") (pin "P$2") (pinfunction "6_P$2") (pintype "passive"))
    )
    (net (code "48") (name "Net-(U$14-PadA)") (class "Default")
      (node (ref "U$14") (pin "A") (pinfunction "A_A") (pintype "passive"))
      (node (ref "U$15") (pin "C") (pinfunction "C_C") (pintype "passive"))
    )
    (net (code "49") (name "Net-(U$15-PadA)") (class "Default")
      (node (ref "U$15") (pin "A") (pinfunction "A_A") (pintype "passive"))
      (node (ref "U$16") (pin "C") (pinfunction "C_C") (pintype "passive"))
    )
    (net (code "50") (name "Net-(U$16-PadA)") (class "Default")
      (node (ref "U$16") (pin "A") (pinfunction "A_A") (pintype "passive"))
      (node (ref "U$17") (pin "C") (pinfunction "C_C") (pintype "passive"))
    )
    (net (code "51") (name "Net-(U$18-PadC)") (class "Default")
      (node (ref "U$18") (pin "C") (pinfunction "C_C") (pintype "passive"))
      (node (ref "U$19") (pin "A") (pinfunction "A_A") (pintype "passive"))
    )
    (net (code "52") (name "Net-(U$19-PadC)") (class "Default")
      (node (ref "U$19") (pin "C") (pinfunction "C_C") (pintype "passive"))
      (node (ref "U$20") (pin "A") (pinfunction "A_A") (pintype "passive"))
    )
    (net (code "53") (name "Net-(U$20-PadC)") (class "Default")
      (node (ref "U$20") (pin "C") (pinfunction "C_C") (pintype "passive"))
      (node (ref "U$21") (pin "A") (pinfunction "A_A") (pintype "passive"))
    )
    (net (code "54") (name "Net-(U$23-G)") (class "Default")
      (node (ref "D19") (pin "C") (pinfunction "C_C") (pintype "passive"))
      (node (ref "R18") (pin "1") (pinfunction "1_1") (pintype "passive"))
      (node (ref "R20") (pin "2") (pinfunction "2_2") (pintype "passive"))
      (node (ref "U$23") (pin "B") (pinfunction "G_B") (pintype "passive"))
      (node (ref "U$9") (pin "2") (pinfunction "G_2") (pintype "passive"))
    )
    (net (code "55") (name "Net-(U$23-S)") (class "Default")
      (node (ref "R32") (pin "2") (pinfunction "2_2") (pintype "passive"))
      (node (ref "U$23") (pin "E") (pinfunction "S_E") (pintype "passive"))
      (node (ref "U$9") (pin "3") (pinfunction "S_3") (pintype "passive"))
    )
    (net (code "56") (name "Net-(U$24-G)") (class "Default")
      (node (ref "D3") (pin "C") (pinfunction "C_C") (pintype "passive"))
      (node (ref "R1") (pin "1") (pinfunction "1_1") (pintype "passive"))
      (node (ref "R6") (pin "2") (pinfunction "2_2") (pintype "passive"))
      (node (ref "U$24") (pin "B") (pinfunction "G_B") (pintype "passive"))
      (node (ref "U$5") (pin "2") (pinfunction "G_2") (pintype "passive"))
    )
    (net (code "57") (name "Net-(U$24-S)") (class "Default")
      (node (ref "R33") (pin "2") (pinfunction "2_2") (pintype "passive"))
      (node (ref "U$24") (pin "E") (pinfunction "S_E") (pintype "passive"))
      (node (ref "U$5") (pin "3") (pinfunction "S_3") (pintype "passive"))
    )
    (net (code "58") (name "Net-(U$25-G)") (class "Default")
      (node (ref "D7") (pin "C") (pinfunction "C_C") (pintype "passive"))
      (node (ref "R2") (pin "1") (pinfunction "1_1") (pintype "passive"))
      (node (ref "R8") (pin "2") (pinfunction "2_2") (pintype "passive"))
      (node (ref "U$25") (pin "B") (pinfunction "G_B") (pintype "passive"))
      (node (ref "U$4") (pin "2") (pinfunction "G_2") (pintype "passive"))
    )
    (net (code "59") (name "Net-(U$25-S)") (class "Default")
      (node (ref "R34") (pin "2") (pinfunction "2_2") (pintype "passive"))
      (node (ref "U$25") (pin "E") (pinfunction "S_E") (pintype "passive"))
      (node (ref "U$4") (pin "3") (pinfunction "S_3") (pintype "passive"))
    )
    (net (code "60") (name "Net-(U$29-G)") (class "Default")
      (node (ref "D12") (pin "A") (pinfunction "A_A") (pintype "passive"))
      (node (ref "R12") (pin "2") (pinfunction "2_2") (pintype "passive"))
      (node (ref "R5") (pin "1") (pinfunction "1_1") (pintype "passive"))
      (node (ref "U$29") (pin "B") (pinfunction "G_B") (pintype "passive"))
      (node (ref "U$6") (pin "2") (pinfunction "G_2") (pintype "passive"))
    )
    (net (code "61") (name "Net-(U$29-S)") (class "Default")
      (node (ref "R13") (pin "2") (pinfunction "2_2") (pintype "passive"))
      (node (ref "U$29") (pin "E") (pinfunction "S_E") (pintype "passive"))
      (node (ref "U$6") (pin "3") (pinfunction "S_3") (pintype "passive"))
    )
  )
)
